# Sheet2.net
KiCad netlist of a schematic drawn in Altium Designer
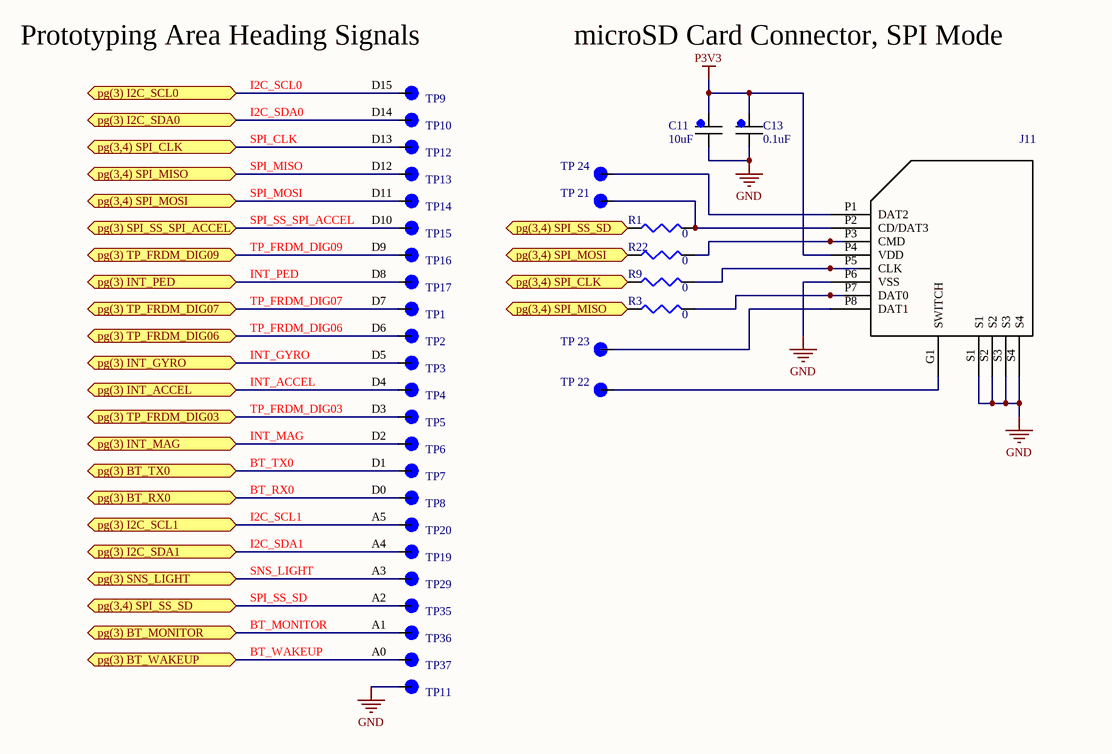
[diagram p0: Sheet2.SchDoc]

(export (version "E")
  (design (tool "Eeschema 10.0.6"))
  (components
    (comp (ref "C11")
      (value "10uF")
      (description "Electrolytic capacitor")
      (fields (field (name "Comment") "E_Cap"))
      (libsource (lib "Schlib2") (part "E_Cap"))
    )
    (comp (ref "C13")
      (value "0.1uF")
      (description "Electrolytic capacitor")
      (fields (field (name "Comment") "E_Cap"))
      (libsource (lib "Schlib2") (part "E_Cap"))
    )
    (comp (ref "J11")
      (value "J11")
      (footprint "105162-0001")
      (description "CON microSD")
      (libsource (lib "Schlib2") (part "J11"))
    )
    (comp (ref "R1")
      (value "0")
      (footprint "J1-0603")
      (description "Resistor")
      (fields (field (name "Comment") "Res3") (field (name "PUBLISHER") "Altium Limited"))
      (libsource (lib "Miscellaneous Devices") (part "Res3"))
    )
    (comp (ref "R3")
      (value "0")
      (footprint "J1-0603")
      (description "Resistor")
      (fields (field (name "Comment") "Res3") (field (name "PUBLISHER") "Altium Limited"))
      (libsource (lib "Miscellaneous Devices") (part "Res3"))
    )
    (comp (ref "R9")
      (value "0")
      (footprint "J1-0603")
      (description "Resistor")
      (fields (field (name "Comment") "Res3") (field (name "PUBLISHER") "Altium Limited"))
      (libsource (lib "Miscellaneous Devices") (part "Res3"))
    )
    (comp (ref "R22")
      (value "0")
      (footprint "J1-0603")
      (description "Resistor")
      (fields (field (name "Comment") "Res3") (field (name "PUBLISHER") "Altium Limited"))
      (libsource (lib "Miscellaneous Devices") (part "Res3"))
    )
    (comp (ref "TP 21") (value "TP") (libsource (lib "Schlib2") (part "TP")))
    (comp (ref "TP 22") (value "TP") (libsource (lib "Schlib2") (part "TP")))
    (comp (ref "TP 23") (value "TP") (libsource (lib "Schlib2") (part "TP")))
    (comp (ref "TP 24") (value "TP") (libsource (lib "Schlib2") (part "TP")))
    (comp (ref "TP1") (value "TP") (libsource (lib "Schlib2") (part "TP")))
    (comp (ref "TP2") (value "TP") (libsource (lib "Schlib2") (part "TP")))
    (comp (ref "TP3") (value "TP") (libsource (lib "Schlib2") (part "TP")))
    (comp (ref "TP4") (value "TP") (libsource (lib "Schlib2") (part "TP")))
    (comp (ref "TP5") (value "TP") (libsource (lib "Schlib2") (part "TP")))
    (comp (ref "TP6") (value "TP") (libsource (lib "Schlib2") (part "TP")))
    (comp (ref "TP7") (value "TP") (libsource (lib "Schlib2") (part "TP")))
    (comp (ref "TP8") (value "TP") (libsource (lib "Schlib2") (part "TP")))
    (comp (ref "TP9") (value "TP") (libsource (lib "Schlib2") (part "TP")))
    (comp (ref "TP10") (value "TP") (libsource (lib "Schlib2") (part "TP")))
    (comp (ref "TP11") (value "TP") (libsource (lib "Schlib2") (part "TP")))
    (comp (ref "TP12") (value "TP") (libsource (lib "Schlib2") (part "TP")))
    (comp (ref "TP13") (value "TP") (libsource (lib "Schlib2") (part "TP")))
    (comp (ref "TP14") (value "TP") (libsource (lib "Schlib2") (part "TP")))
    (comp (ref "TP15") (value "TP") (libsource (lib "Schlib2") (part "TP")))
    (comp (ref "TP16") (value "TP") (libsource (lib "Schlib2") (part "TP")))
    (comp (ref "TP17") (value "TP") (libsource (lib "Schlib2") (part "TP")))
    (comp (ref "TP19") (value "TP") (libsource (lib "Schlib2") (part "TP")))
    (comp (ref "TP20") (value "TP") (libsource (lib "Schlib2") (part "TP")))
    (comp (ref "TP29") (value "TP") (libsource (lib "Schlib2") (part "TP")))
    (comp (ref "TP35") (value "TP") (libsource (lib "Schlib2") (part "TP")))
    (comp (ref "TP36") (value "TP") (libsource (lib "Schlib2") (part "TP")))
    (comp (ref "TP37") (value "TP") (libsource (lib "Schlib2") (part "TP")))
  )
  (nets
    (net (code "1") (name "/pg(3) BT_MONITOR") (class "Default")
      (node (ref "TP36") (pin "1") (pinfunction "1_1") (pintype "passive"))
    )
    (net (code "2") (name "/pg(3) BT_RX0") (class "Default")
      (node (ref "TP8") (pin "1") (pinfunction "1_1") (pintype "passive"))
    )
    (net (code "3") (name "/pg(3) BT_TX0") (class "Default")
      (node (ref "TP7") (pin "1") (pinfunction "1_1") (pintype "passive"))
    )
    (net (code "4") (name "/pg(3) BT_WAKEUP") (class "Default")
      (node (ref "TP37") (pin "1") (pinfunction "1_1") (pintype "passive"))
    )
    (net (code "5") (name "/pg(3) I2C_SCL0") (class "Default")
      (node (ref "TP9") (pin "1") (pinfunction "1_1") (pintype "passive"))
    )
    (net (code "6") (name "/pg(3) I2C_SCL1") (class "Default")
      (node (ref "TP20") (pin "1") (pinfunction "1_1") (pintype "passive"))
    )
    (net (code "7") (name "/pg(3) I2C_SDA0") (class "Default")
      (node (ref "TP10") (pin "1") (pinfunction "1_1") (pintype "passive"))
    )
    (net (code "8") (name "/pg(3) I2C_SDA1") (class "Default")
      (node (ref "TP19") (pin "1") (pinfunction "1_1") (pintype "passive"))
    )
    (net (code "9") (name "/pg(3) INT_ACCEL") (class "Default")
      (node (ref "TP4") (pin "1") (pinfunction "1_1") (pintype "passive"))
    )
    (net (code "10") (name "/pg(3) INT_GYRO") (class "Default")
      (node (ref "TP3") (pin "1") (pinfunction "1_1") (pintype "passive"))
    )
    (net (code "11") (name "/pg(3) INT_MAG") (class "Default")
      (node (ref "TP6") (pin "1") (pinfunction "1_1") (pintype "passive"))
    )
    (net (code "12") (name "/pg(3) INT_PED") (class "Default")
      (node (ref "TP17") (pin "1") (pinfunction "1_1") (pintype "passive"))
    )
    (net (code "13") (name "/pg(3) SNS_LIGHT") (class "Default")
      (node (ref "TP29") (pin "1") (pinfunction "1_1") (pintype "passive"))
    )
    (net (code "14") (name "/pg(3) SPI_SS_SPI_ACCEL") (class "Default")
      (node (ref "TP15") (pin "1") (pinfunction "1_1") (pintype "passive"))
    )
    (net (code "15") (name "/pg(3) TP_FRDM_DIG03") (class "Default")
      (node (ref "TP5") (pin "1") (pinfunction "1_1") (pintype "passive"))
    )
    (net (code "16") (name "/pg(3) TP_FRDM_DIG06") (class "Default")
      (node (ref "TP2") (pin "1") (pinfunction "1_1") (pintype "passive"))
    )
    (net (code "17") (name "/pg(3) TP_FRDM_DIG07") (class "Default")
      (node (ref "TP1") (pin "1") (pinfunction "1_1") (pintype "passive"))
    )
    (net (code "18") (name "/pg(3) TP_FRDM_DIG09") (class "Default")
      (node (ref "TP16") (pin "1") (pinfunction "1_1") (pintype "passive"))
    )
    (net (code "19") (name "/pg(3,4) SPI_CLK") (class "Default")
      (node (ref "R9") (pin "1") (pinfunction "1_1") (pintype "passive"))
      (node (ref "TP12") (pin "1") (pinfunction "1_1") (pintype "passive"))
    )
    (net (code "20") (name "/pg(3,4) SPI_MISO") (class "Default")
      (node (ref "R3") (pin "1") (pinfunction "1_1") (pintype "passive"))
      (node (ref "TP13") (pin "1") (pinfunction "1_1") (pintype "passive"))
    )
    (net (code "21") (name "/pg(3,4) SPI_MOSI") (class "Default")
      (node (ref "R22") (pin "1") (pinfunction "1_1") (pintype "passive"))
      (node (ref "TP14") (pin "1") (pinfunction "1_1") (pintype "passive"))
    )
    (net (code "22") (name "/pg(3,4) SPI_SS_SD") (class "Default")
      (node (ref "R1") (pin "1") (pinfunction "1_1") (pintype "passive"))
      (node (ref "TP35") (pin "1") (pinfunction "1_1") (pintype "passive"))
    )
    (net (code "23") (name "GND") (class "Default")
      (node (ref "C11") (pin "7") (pinfunction "7_7") (pintype "passive"))
      (node (ref "C13") (pin "7") (pinfunction "7_7") (pintype "passive"))
      (node (ref "J11") (pin "P6") (pinfunction "VSS_P6") (pintype "passive"))
      (node (ref "J11") (pin "S1") (pinfunction "S1_S1") (pintype "passive"))
      (node (ref "J11") (pin "S2") (pinfunction "S2_S2") (pintype "passive"))
      (node (ref "J11") (pin "S3") (pinfunction "S3_S3") (pintype "passive"))
      (node (ref "J11") (pin "S4") (pinfunction "S4_S4") (pintype "passive"))
      (node (ref "TP11") (pin "1") (pinfunction "1_1") (pintype "passive"))
    )
    (net (code "24") (name "Net-(J11-CD{slash}DAT3)") (class "Default")
      (node (ref "J11") (pin "P2") (pinfunction "CD/DAT3_P2") (pintype "passive"))
      (node (ref "R1") (pin "2") (pinfunction "2_2") (pintype "passive"))
      (node (ref "TP 21") (pin "1") (pinfunction "1_1") (pintype "passive"))
    )
    (net (code "25") (name "Net-(J11-CLK)") (class "Default")
      (node (ref "J11") (pin "P5") (pinfunction "CLK_P5") (pintype "passive"))
      (node (ref "R9") (pin "2") (pinfunction "2_2") (pintype "passive"))
    )
    (net (code "26") (name "Net-(J11-CMD)") (class "Default")
      (node (ref "J11") (pin "P3") (pinfunction "CMD_P3") (pintype "passive"))
      (node (ref "R22") (pin "2") (pinfunction "2_2") (pintype "passive"))
    )
    (net (code "27") (name "Net-(J11-DAT0)") (class "Default")
      (node (ref "J11") (pin "P7") (pinfunction "DAT0_P7") (pintype "passive"))
      (node (ref "R3") (pin "2") (pinfunction "2_2") (pintype "passive"))
    )
    (net (code "28") (name "Net-(J11-DAT1)") (class "Default")
      (node (ref "J11") (pin "P8") (pinfunction "DAT1_P8") (pintype "passive"))
      (node (ref "TP 23") (pin "1") (pinfunction "1_1") (pintype "passive"))
    )
    (net (code "29") (name "Net-(J11-DAT2)") (class "Default")
      (node (ref "J11") (pin "P1") (pinfunction "DAT2_P1") (pintype "passive"))
      (node (ref "TP 24") (pin "1") (pinfunction "1_1") (pintype "passive"))
    )
    (net (code "30") (name "Net-(J11-SWITCH)") (class "Default")
      (node (ref "J11") (pin "G1") (pinfunction "SWITCH_G1") (pintype "passive"))
      (node (ref "TP 22") (pin "1") (pinfunction "1_1") (pintype "passive"))
    )
    (net (code "31") (name "P3V3") (class "Default")
      (node (ref "C11") (pin "8") (pinfunction "8_8") (pintype "passive"))
      (node (ref "C13") (pin "8") (pinfunction "8_8") (pintype "passive"))
      (node (ref "J11") (pin "P4") (pinfunction "VDD_P4") (pintype "passive"))
    )
  )
)
